# Ex_EEPROM.net
KiCad netlist of a schematic drawn in EAGLE
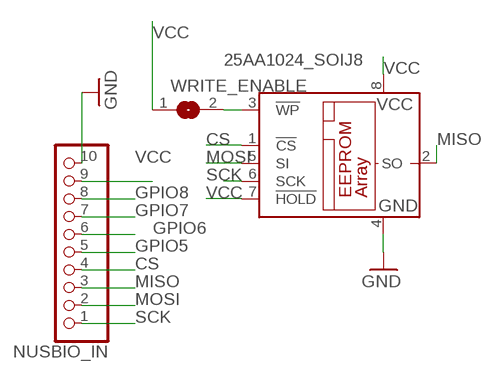
[diagram p0: schematic, sheet 1]

(export (version "E")
  (design (tool "Eeschema 10.0.6"))
  (components
    (comp (ref "25AA1024_SOIJ8")
      (value "25AA080SN")
      (footprint "eagle-import:SO-08")
      (fields (field (name "MF") "MICROCHIP") (field (name "MPN") "25AA080/SN"))
      (libsource (lib "eagle-import") (part "25SNAA080"))
    )
    (comp (ref "NUSBIO_IN")
      (value "PINHD-1X10")
      (footprint "eagle-import:1X10-BIG")
      (libsource (lib "eagle-import") (part "PINHD-1X10"))
    )
    (comp (ref "WRITE_ENABLE")
      (value "SOLDERJUMPERREFLOW")
      (footprint "eagle-import:SOLDERJUMPER_REFLOW")
      (libsource (lib "eagle-import") (part "SOLDERJUMPERREFLOW"))
    )
  )
  (nets
    (net (code "1") (name "/CS") (class "Default")
      (node (ref "25AA1024_SOIJ8") (pin "1") (pinfunction "~{CS}_1") (pintype "input"))
      (node (ref "NUSBIO_IN") (pin "4") (pinfunction "4_4") (pintype "passive"))
    )
    (net (code "2") (name "/GPIO5") (class "Default")
      (node (ref "NUSBIO_IN") (pin "5") (pinfunction "5_5") (pintype "passive"))
    )
    (net (code "3") (name "/GPIO6") (class "Default")
      (node (ref "NUSBIO_IN") (pin "6") (pinfunction "6_6") (pintype "passive"))
    )
    (net (code "4") (name "/GPIO7") (class "Default")
      (node (ref "NUSBIO_IN") (pin "7") (pinfunction "7_7") (pintype "passive"))
    )
    (net (code "5") (name "/GPIO8") (class "Default")
      (node (ref "NUSBIO_IN") (pin "8") (pinfunction "8_8") (pintype "passive"))
    )
    (net (code "6") (name "/MISO") (class "Default")
      (node (ref "25AA1024_SOIJ8") (pin "2") (pinfunction "SO_2") (pintype "bidirectional"))
      (node (ref "NUSBIO_IN") (pin "3") (pinfunction "3_3") (pintype "passive"))
    )
    (net (code "7") (name "/MOSI") (class "Default")
      (node (ref "25AA1024_SOIJ8") (pin "5") (pinfunction "SI_5") (pintype "input"))
      (node (ref "NUSBIO_IN") (pin "2") (pinfunction "2_2") (pintype "passive"))
    )
    (net (code "8") (name "/SCK") (class "Default")
      (node (ref "25AA1024_SOIJ8") (pin "6") (pinfunction "SCK_6") (pintype "input"))
      (node (ref "NUSBIO_IN") (pin "1") (pinfunction "1_1") (pintype "passive"))
    )
    (net (code "9") (name "/VCC") (class "Default")
      (node (ref "25AA1024_SOIJ8") (pin "7") (pinfunction "~{HOLD}_7") (pintype "input"))
      (node (ref "25AA1024_SOIJ8") (pin "8") (pinfunction "VCC_8") (pintype "power_in"))
      (node (ref "NUSBIO_IN") (pin "9") (pinfunction "9_9") (pintype "passive"))
      (node (ref "WRITE_ENABLE") (pin "1") (pinfunction "1_1") (pintype "passive"))
    )
    (net (code "10") (name "GND") (class "Default")
      (node (ref "25AA1024_SOIJ8") (pin "4") (pinfunction "GND_4") (pintype "power_in"))
      (node (ref "NUSBIO_IN") (pin "10") (pinfunction "10_10") (pintype "passive"))
    )
    (net (code "11") (name "Net-(25AA1024_SOIJ8-~{WP})") (class "Default")
      (node (ref "25AA1024_SOIJ8") (pin "3") (pinfunction "~{WP}_3") (pintype "input"))
      (node (ref "WRITE_ENABLE") (pin "2") (pinfunction "2_2") (pintype "passive"))
    )
  )
)
